# Mainland.net
KiCad netlist of a schematic drawn in EAGLE
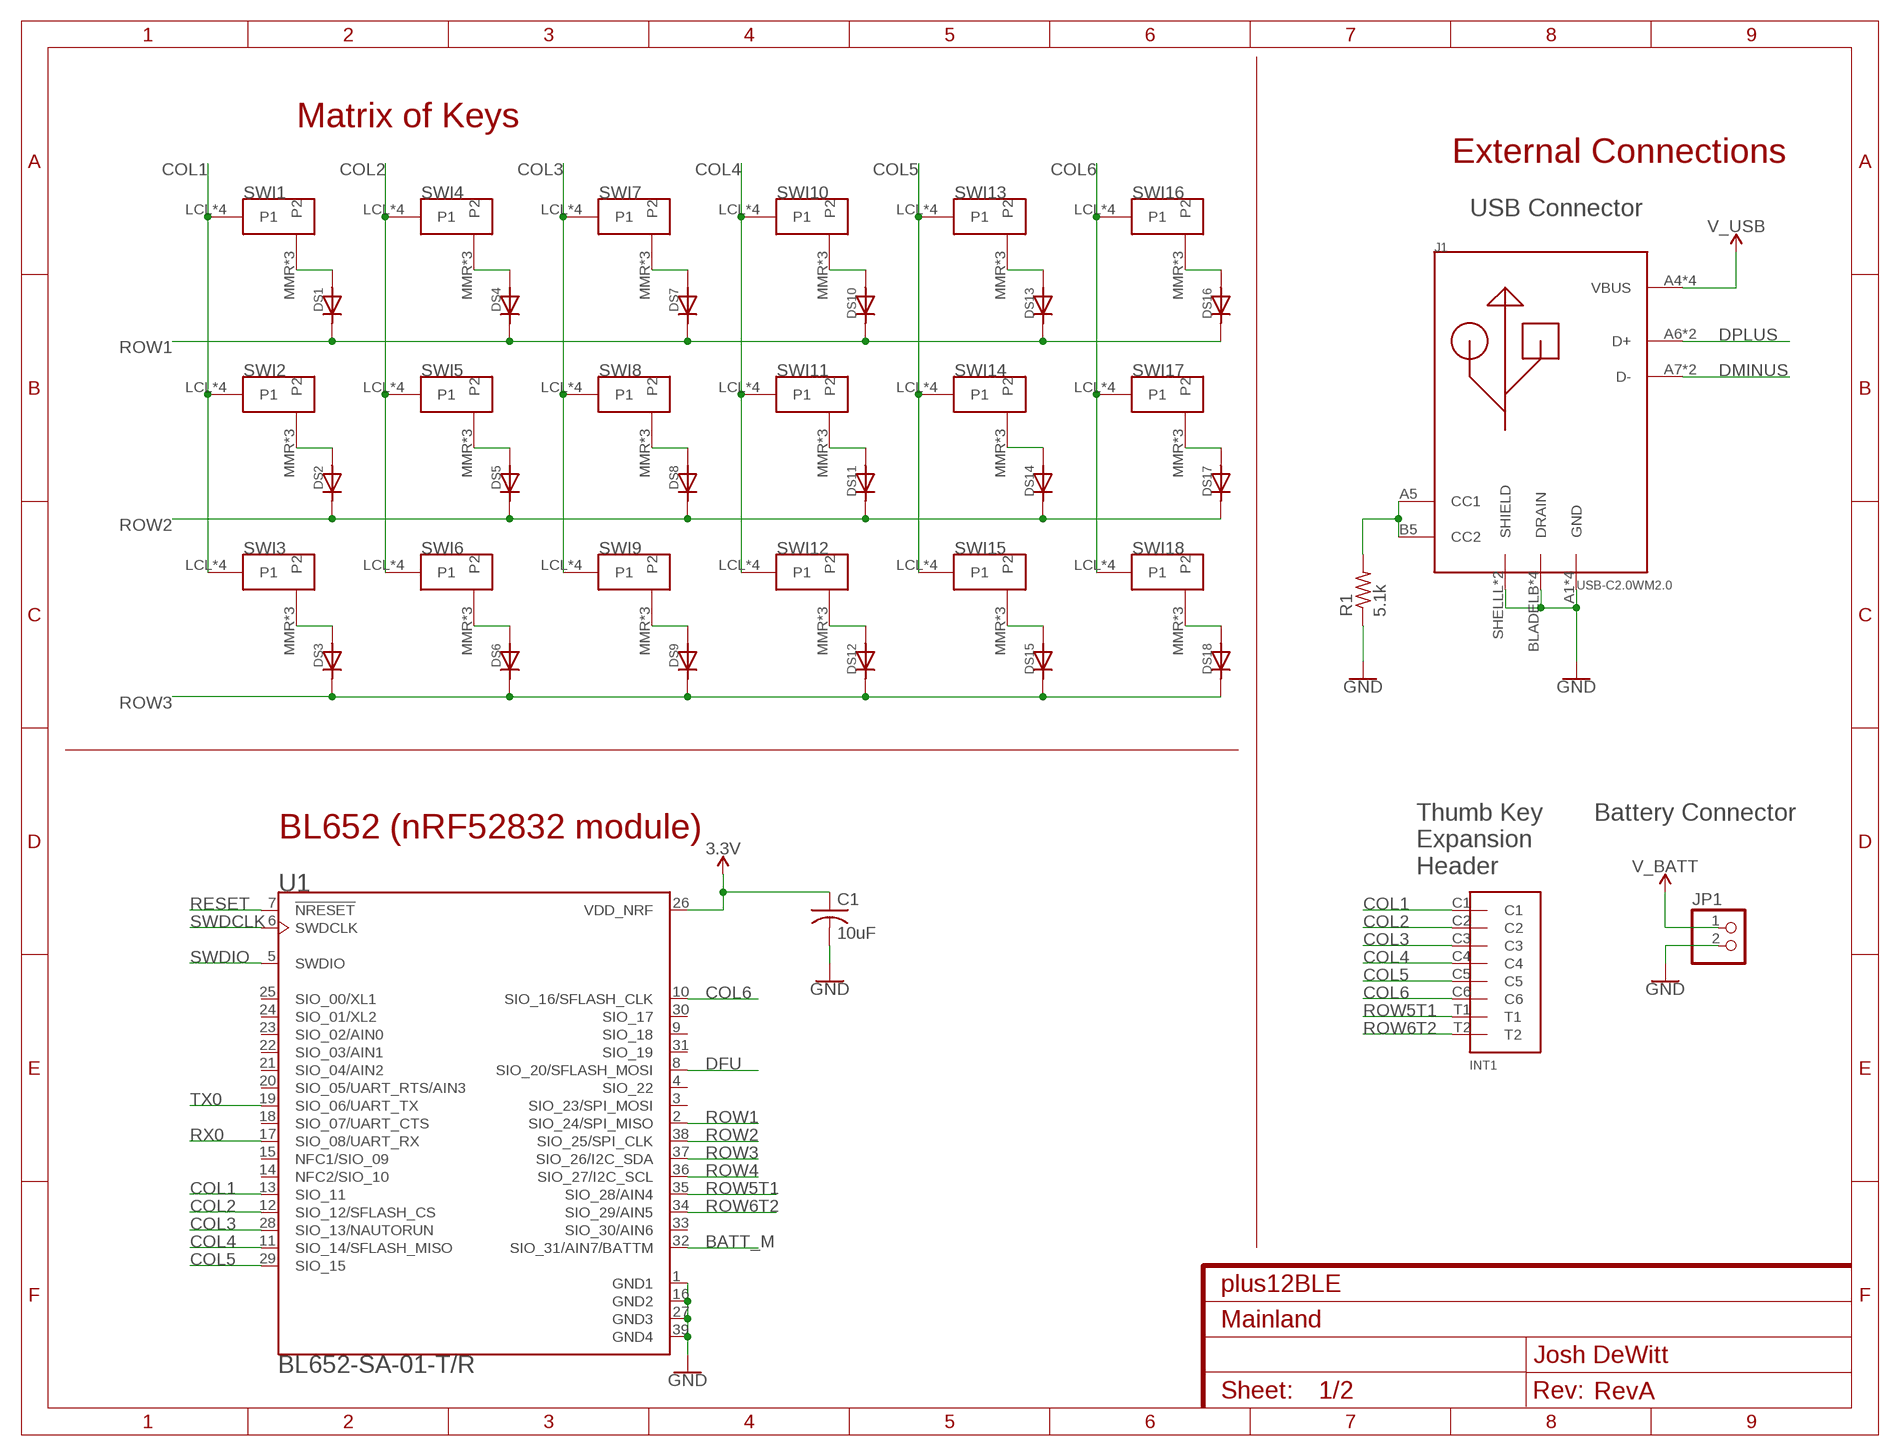
[diagram p0: schematic, sheet 1]
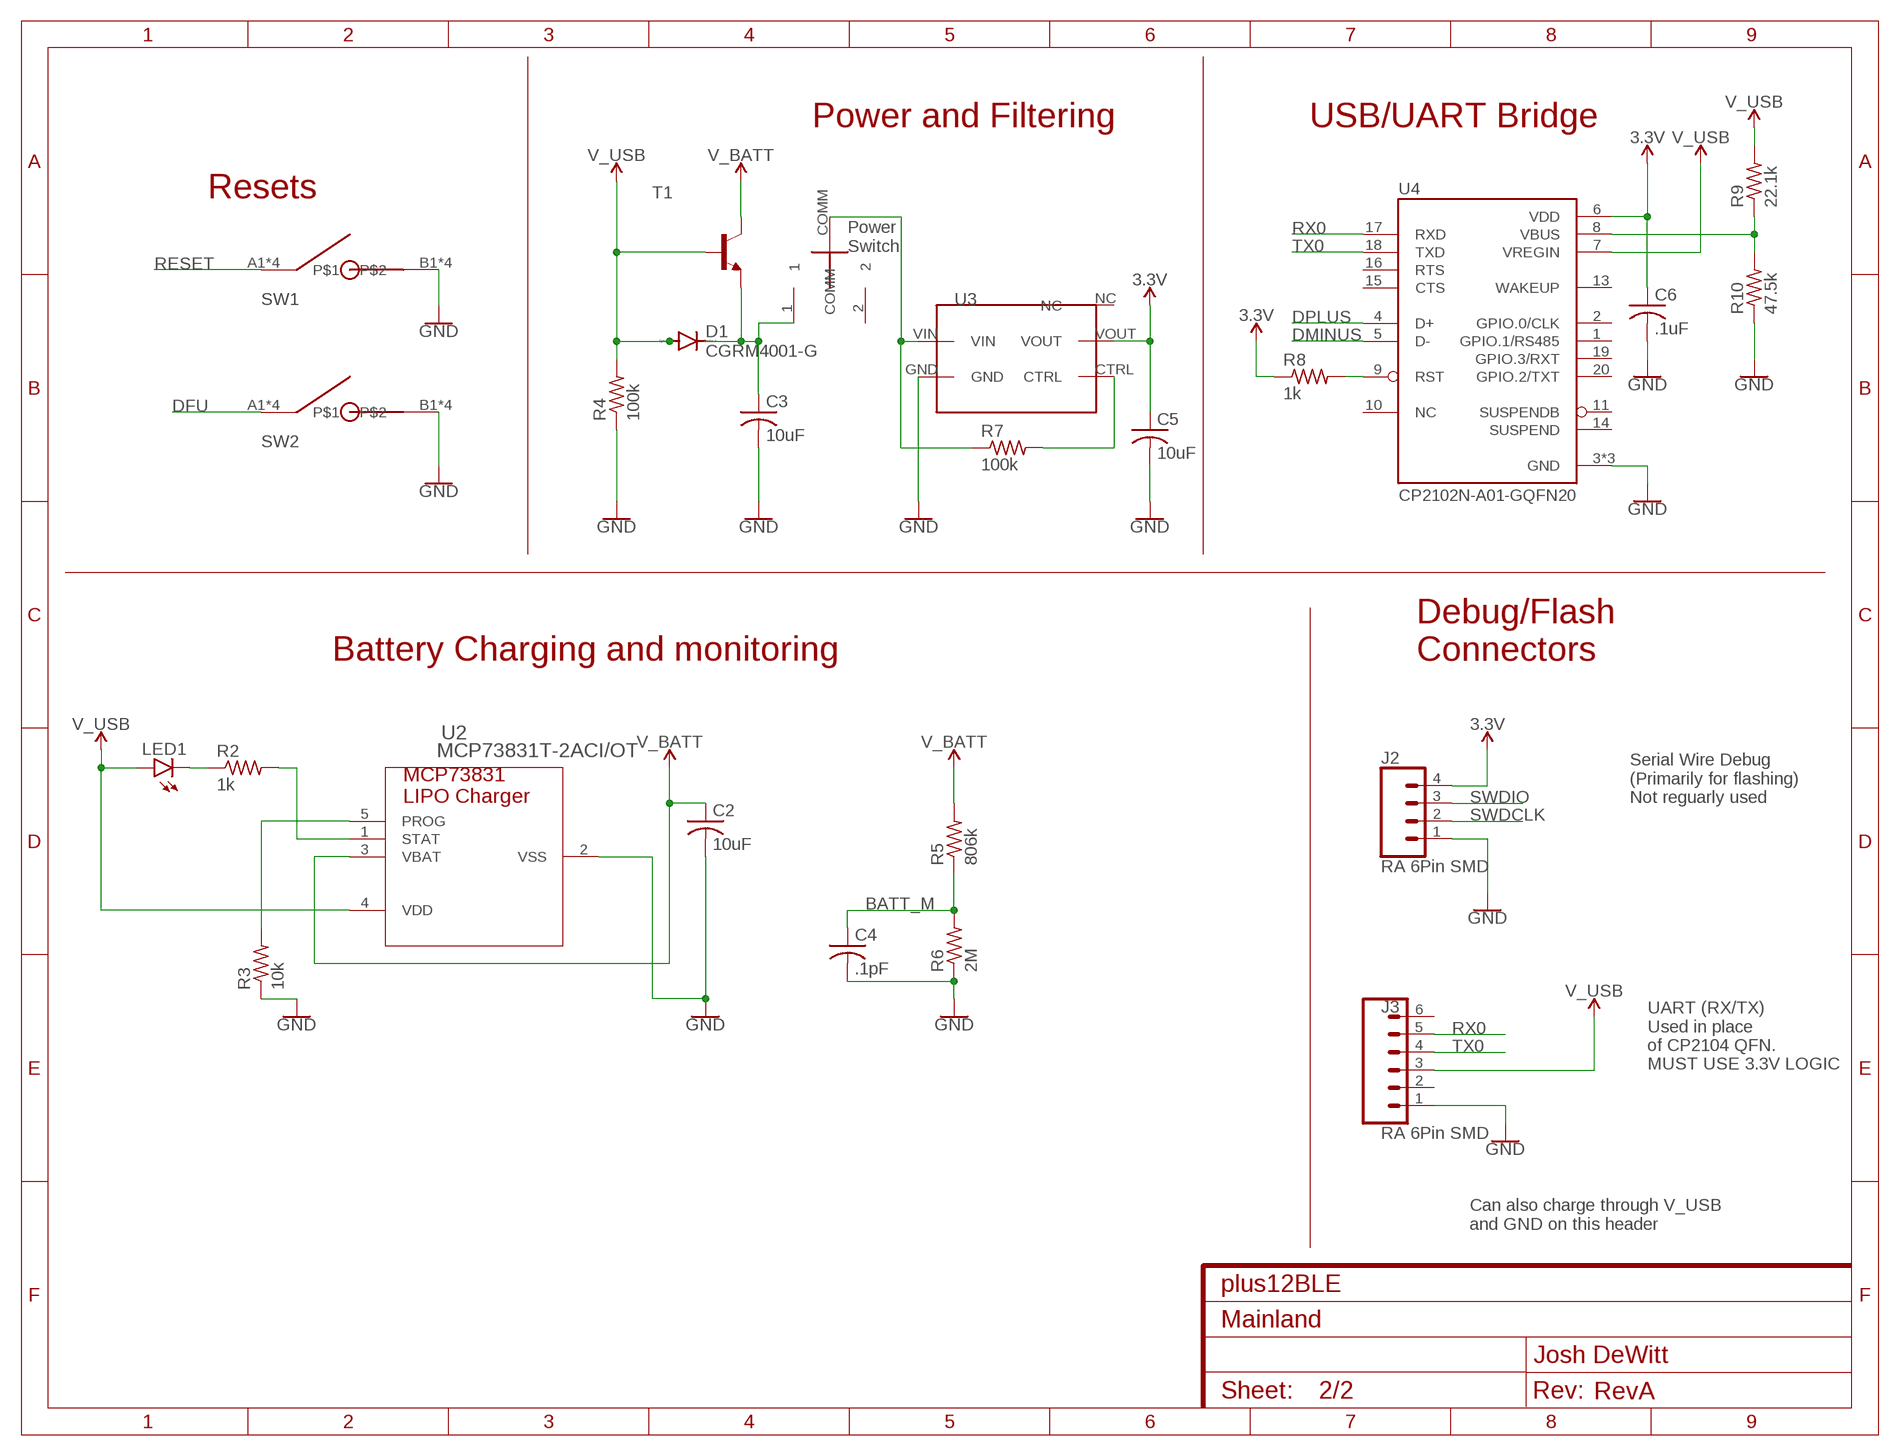
[diagram p1: schematic, sheet 2]

(export (version "E")
  (design (tool "Eeschema 10.0.6"))
  (components
    (comp (ref "C2")
      (value "10uF")
      (footprint "eagle-import:C0805K")
      (libsource (lib "eagle-import") (part "C-USC0805K"))
    )
    (comp (ref "C3")
      (value "10uF")
      (footprint "eagle-import:C0805K")
      (libsource (lib "eagle-import") (part "C-USC0805K"))
    )
    (comp (ref "C4")
      (value ".1pF")
      (footprint "eagle-import:C0603")
      (libsource (lib "eagle-import") (part "C-USC0603"))
    )
    (comp (ref "C5")
      (value "10uF")
      (footprint "eagle-import:C0805K")
      (libsource (lib "eagle-import") (part "C-USC0805K"))
    )
    (comp (ref "C6")
      (value ".1uF")
      (footprint "eagle-import:C0603")
      (libsource (lib "eagle-import") (part "C-USC0603"))
    )
    (comp (ref "D1")
      (value "CGRM4001-G")
      (footprint "eagle-import:SOD-123_MINI-SMA")
      (libsource (lib "eagle-import") (part "CGRM400-G1"))
    )
    (comp (ref "FRAME2")
      (value "FRAME_LTR_CU_MARK")
      (footprint "eagle-import:FR-LTR-ON-PCB")
      (libsource (lib "eagle-import") (part "FRAME_LTR_CU_MARK"))
    )
    (comp (ref "J2")
      (value "RA 6Pin SMD")
      (footprint "eagle-import:1X04_SMD_RA_FEMALE")
      (libsource (lib "eagle-import") (part "CONN_04SMD_RA_FEMALE"))
    )
    (comp (ref "J3")
      (value "RA 6Pin SMD")
      (footprint "eagle-import:1X06-SMD_RA_MALE")
      (libsource (lib "eagle-import") (part "CONN_06SMD"))
    )
    (comp (ref "LED1")
      (value "LEDCHIP-LED0603")
      (footprint "eagle-import:CHIP-LED0603")
      (libsource (lib "eagle-import") (part "LEDCHIP-LED0603"))
    )
    (comp (ref "R2")
      (value "1k")
      (footprint "eagle-import:R0603")
      (libsource (lib "eagle-import") (part "R-US_R0603"))
    )
    (comp (ref "R3")
      (value "10k")
      (footprint "eagle-import:R0603")
      (libsource (lib "eagle-import") (part "R-US_R0603"))
    )
    (comp (ref "R4")
      (value "100k")
      (footprint "eagle-import:R0603")
      (libsource (lib "eagle-import") (part "R-US_R0603"))
    )
    (comp (ref "R5")
      (value "806k")
      (footprint "eagle-import:R0603")
      (libsource (lib "eagle-import") (part "R-US_R0603"))
    )
    (comp (ref "R6")
      (value "2M")
      (footprint "eagle-import:R0603")
      (libsource (lib "eagle-import") (part "R-US_R0603"))
    )
    (comp (ref "R7")
      (value "100k")
      (footprint "eagle-import:R0603")
      (libsource (lib "eagle-import") (part "R-US_R0603"))
    )
    (comp (ref "R8")
      (value "1k")
      (footprint "eagle-import:R0603")
      (libsource (lib "eagle-import") (part "R-US_R0603"))
    )
    (comp (ref "R9")
      (value "22.1k")
      (footprint "eagle-import:R0603")
      (libsource (lib "eagle-import") (part "R-US_R0603"))
    )
    (comp (ref "R10")
      (value "47.5k")
      (footprint "eagle-import:R0603")
      (libsource (lib "eagle-import") (part "R-US_R0603"))
    )
    (comp (ref "SW1")
      (value "RSTSWSMALL_SMD")
      (footprint "eagle-import:EVP-BBA")
      (libsource (lib "eagle-import") (part "RSTSWSMALL_SMD"))
    )
    (comp (ref "SW2")
      (value "RSTSWSMALL_SMD")
      (footprint "eagle-import:EVP-BBA")
      (libsource (lib "eagle-import") (part "RSTSWSMALL_SMD"))
    )
    (comp (ref "SW3")
      (value "SLIDER_SWITCH")
      (footprint "eagle-import:MHSS1105")
      (libsource (lib "eagle-import") (part "SLIDER_SWITCH"))
    )
    (comp (ref "T1")
      (value "BC808-NPN-SOT23-BEC")
      (footprint "eagle-import:SOT23-BEC")
      (libsource (lib "eagle-import") (part "-NPN-SOT23-BECBC808"))
    )
    (comp (ref "U2")
      (value "MCP73831T-2ACI/OT")
      (footprint "eagle-import:SOT-23-5_MC")
      (fields (field (name "MANUFACTURER_PART_NUMBER") "MCP73831T2ACIOT"))
      (libsource (lib "eagle-import") (part "MCP73831T-2ACI/OT"))
    )
    (comp (ref "U3")
      (value "TCR2EF")
      (footprint "eagle-import:TCR2EF")
      (libsource (lib "eagle-import") (part "TCR2EF"))
    )
    (comp (ref "U4")
      (value "CP2102N-A01-GQFN20")
      (footprint "eagle-import:SILABS_QFN20")
      (fields (field (name "DIGI-KEY_PART_NUMBER") "336-3692-ND") (field (name "MF") "Silicon Labs"))
      (libsource (lib "eagle-import") (part "CP2102N-A01-GQFN20"))
    )
    (comp (ref "C1")
      (value "10uF")
      (footprint "eagle-import:C0805K")
      (libsource (lib "eagle-import") (part "C-USC0805K"))
    )
    (comp (ref "DS1")
      (value "DIODECOMBO")
      (footprint "eagle-import:DIODE_COMBO")
      (libsource (lib "eagle-import") (part "DIODECOMBO"))
    )
    (comp (ref "DS2")
      (value "DIODECOMBO")
      (footprint "eagle-import:DIODE_COMBO")
      (libsource (lib "eagle-import") (part "DIODECOMBO"))
    )
    (comp (ref "DS3")
      (value "DIODECOMBO")
      (footprint "eagle-import:DIODE_COMBO")
      (libsource (lib "eagle-import") (part "DIODECOMBO"))
    )
    (comp (ref "DS4")
      (value "DIODECOMBO")
      (footprint "eagle-import:DIODE_COMBO")
      (libsource (lib "eagle-import") (part "DIODECOMBO"))
    )
    (comp (ref "DS5")
      (value "DIODECOMBO")
      (footprint "eagle-import:DIODE_COMBO")
      (libsource (lib "eagle-import") (part "DIODECOMBO"))
    )
    (comp (ref "DS6")
      (value "DIODECOMBO")
      (footprint "eagle-import:DIODE_COMBO")
      (libsource (lib "eagle-import") (part "DIODECOMBO"))
    )
    (comp (ref "DS7")
      (value "DIODECOMBO")
      (footprint "eagle-import:DIODE_COMBO")
      (libsource (lib "eagle-import") (part "DIODECOMBO"))
    )
    (comp (ref "DS8")
      (value "DIODECOMBO")
      (footprint "eagle-import:DIODE_COMBO")
      (libsource (lib "eagle-import") (part "DIODECOMBO"))
    )
    (comp (ref "DS9")
      (value "DIODECOMBO")
      (footprint "eagle-import:DIODE_COMBO")
      (libsource (lib "eagle-import") (part "DIODECOMBO"))
    )
    (comp (ref "DS10")
      (value "DIODECOMBO")
      (footprint "eagle-import:DIODE_COMBO")
      (libsource (lib "eagle-import") (part "DIODECOMBO"))
    )
    (comp (ref "DS11")
      (value "DIODECOMBO")
      (footprint "eagle-import:DIODE_COMBO")
      (libsource (lib "eagle-import") (part "DIODECOMBO"))
    )
    (comp (ref "DS12")
      (value "DIODECOMBO")
      (footprint "eagle-import:DIODE_COMBO")
      (libsource (lib "eagle-import") (part "DIODECOMBO"))
    )
    (comp (ref "DS13")
      (value "DIODECOMBO")
      (footprint "eagle-import:DIODE_COMBO")
      (libsource (lib "eagle-import") (part "DIODECOMBO"))
    )
    (comp (ref "DS14")
      (value "DIODECOMBO")
      (footprint "eagle-import:DIODE_COMBO")
      (libsource (lib "eagle-import") (part "DIODECOMBO"))
    )
    (comp (ref "DS15")
      (value "DIODECOMBO")
      (footprint "eagle-import:DIODE_COMBO")
      (libsource (lib "eagle-import") (part "DIODECOMBO"))
    )
    (comp (ref "DS16")
      (value "DIODECOMBO")
      (footprint "eagle-import:DIODE_COMBO")
      (libsource (lib "eagle-import") (part "DIODECOMBO"))
    )
    (comp (ref "DS17")
      (value "DIODECOMBO")
      (footprint "eagle-import:DIODE_COMBO")
      (libsource (lib "eagle-import") (part "DIODECOMBO"))
    )
    (comp (ref "DS18")
      (value "DIODECOMBO")
      (footprint "eagle-import:DIODE_COMBO")
      (libsource (lib "eagle-import") (part "DIODECOMBO"))
    )
    (comp (ref "FRAME1")
      (value "FRAME_LTR_CU_MARK")
      (footprint "eagle-import:FR-LTR-ON-PCB")
      (libsource (lib "eagle-import") (part "FRAME_LTR_CU_MARK"))
    )
    (comp (ref "INT1")
      (value "INTRCNNT4X2")
      (footprint "eagle-import:INTRRIBBON")
      (libsource (lib "eagle-import") (part "INTRCNNT4X2"))
    )
    (comp (ref "J1")
      (value "USB-C2.0WM2.0")
      (footprint "eagle-import:WM17904_SIMP")
      (libsource (lib "eagle-import") (part "USB-C2.0WM2.0"))
    )
    (comp (ref "JP1")
      (value "PINHD-1X2")
      (footprint "eagle-import:1X02")
      (libsource (lib "eagle-import") (part "PINHD-1X2"))
    )
    (comp (ref "R1")
      (value "5.1k")
      (footprint "eagle-import:R0603")
      (libsource (lib "eagle-import") (part "R-US_R0603"))
    )
    (comp (ref "SWI1")
      (value "MX/ALPSDOUBLE_SLOT")
      (footprint "eagle-import:DOUBLED_SLOTS")
      (libsource (lib "eagle-import") (part "MX/ALPSDOUBLE_SLOT"))
    )
    (comp (ref "SWI2")
      (value "MX/ALPSDOUBLE_SLOT")
      (footprint "eagle-import:DOUBLED_SLOTS")
      (libsource (lib "eagle-import") (part "MX/ALPSDOUBLE_SLOT"))
    )
    (comp (ref "SWI3")
      (value "MX/ALPSDOUBLE_SLOT")
      (footprint "eagle-import:DOUBLED_SLOTS")
      (libsource (lib "eagle-import") (part "MX/ALPSDOUBLE_SLOT"))
    )
    (comp (ref "SWI4")
      (value "MX/ALPSDOUBLE_SLOT")
      (footprint "eagle-import:DOUBLED_SLOTS")
      (libsource (lib "eagle-import") (part "MX/ALPSDOUBLE_SLOT"))
    )
    (comp (ref "SWI5")
      (value "MX/ALPSDOUBLE_SLOT")
      (footprint "eagle-import:DOUBLED_SLOTS")
      (libsource (lib "eagle-import") (part "MX/ALPSDOUBLE_SLOT"))
    )
    (comp (ref "SWI6")
      (value "MX/ALPSDOUBLE_SLOT")
      (footprint "eagle-import:DOUBLED_SLOTS")
      (libsource (lib "eagle-import") (part "MX/ALPSDOUBLE_SLOT"))
    )
    (comp (ref "SWI7")
      (value "MX/ALPSDOUBLE_SLOT")
      (footprint "eagle-import:DOUBLED_SLOTS")
      (libsource (lib "eagle-import") (part "MX/ALPSDOUBLE_SLOT"))
    )
    (comp (ref "SWI8")
      (value "MX/ALPSDOUBLE_SLOT")
      (footprint "eagle-import:DOUBLED_SLOTS")
      (libsource (lib "eagle-import") (part "MX/ALPSDOUBLE_SLOT"))
    )
    (comp (ref "SWI9")
      (value "MX/ALPSDOUBLE_SLOT")
      (footprint "eagle-import:DOUBLED_SLOTS")
      (libsource (lib "eagle-import") (part "MX/ALPSDOUBLE_SLOT"))
    )
    (comp (ref "SWI10")
      (value "MX/ALPSDOUBLE_SLOT")
      (footprint "eagle-import:DOUBLED_SLOTS")
      (libsource (lib "eagle-import") (part "MX/ALPSDOUBLE_SLOT"))
    )
    (comp (ref "SWI11")
      (value "MX/ALPSDOUBLE_SLOT")
      (footprint "eagle-import:DOUBLED_SLOTS")
      (libsource (lib "eagle-import") (part "MX/ALPSDOUBLE_SLOT"))
    )
    (comp (ref "SWI12")
      (value "MX/ALPSDOUBLE_SLOT")
      (footprint "eagle-import:DOUBLED_SLOTS")
      (libsource (lib "eagle-import") (part "MX/ALPSDOUBLE_SLOT"))
    )
    (comp (ref "SWI13")
      (value "MX/ALPSDOUBLE_SLOT")
      (footprint "eagle-import:DOUBLED_SLOTS")
      (libsource (lib "eagle-import") (part "MX/ALPSDOUBLE_SLOT"))
    )
    (comp (ref "SWI14")
      (value "MX/ALPSDOUBLE_SLOT")
      (footprint "eagle-import:DOUBLED_SLOTS")
      (libsource (lib "eagle-import") (part "MX/ALPSDOUBLE_SLOT"))
    )
    (comp (ref "SWI15")
      (value "MX/ALPSDOUBLE_SLOT")
      (footprint "eagle-import:DOUBLED_SLOTS")
      (libsource (lib "eagle-import") (part "MX/ALPSDOUBLE_SLOT"))
    )
    (comp (ref "SWI16")
      (value "MX/ALPSDOUBLE_SLOT")
      (footprint "eagle-import:DOUBLED_SLOTS")
      (libsource (lib "eagle-import") (part "MX/ALPSDOUBLE_SLOT"))
    )
    (comp (ref "SWI17")
      (value "MX/ALPSDOUBLE_SLOT")
      (footprint "eagle-import:DOUBLED_SLOTS")
      (libsource (lib "eagle-import") (part "MX/ALPSDOUBLE_SLOT"))
    )
    (comp (ref "SWI18")
      (value "MX/ALPSDOUBLE_SLOT")
      (footprint "eagle-import:DOUBLED_SLOTS")
      (libsource (lib "eagle-import") (part "MX/ALPSDOUBLE_SLOT"))
    )
    (comp (ref "U1")
      (value "BL652-SA-01-T/R")
      (footprint "eagle-import:XCVR_BL652-SA-01-T_R")
      (fields (field (name "DIGI-KEY_PART_NUMBER") "BL652-SA-01-CT-ND") (field (name "MF") "Laird -"))
      (libsource (lib "eagle-import") (part "BL652-SA-01-T/R"))
    )
  )
  (nets
    (net (code "1") (name "3.3V") (class "Default")
      (node (ref "C1") (pin "1") (pinfunction "1_1") (pintype "passive"))
      (node (ref "C5") (pin "1") (pinfunction "1_1") (pintype "passive"))
      (node (ref "C6") (pin "1") (pinfunction "1_1") (pintype "passive"))
      (node (ref "J2") (pin "4") (pinfunction "4_4") (pintype "passive"))
      (node (ref "R8") (pin "1") (pinfunction "1_1") (pintype "passive"))
      (node (ref "U1") (pin "26") (pinfunction "VDD_NRF_26") (pintype "power_in"))
      (node (ref "U3") (pin "VOUT") (pinfunction "VOUT_VOUT") (pintype "power_in"))
      (node (ref "U4") (pin "6") (pinfunction "VDD_6") (pintype "power_in"))
    )
    (net (code "2") (name "BATT_M") (class "Default")
      (node (ref "C4") (pin "1") (pinfunction "1_1") (pintype "passive"))
      (node (ref "R5") (pin "1") (pinfunction "1_1") (pintype "passive"))
      (node (ref "R6") (pin "2") (pinfunction "2_2") (pintype "passive"))
      (node (ref "U1") (pin "32") (pinfunction "SIO_31/AIN7/BATTM_32") (pintype "bidirectional"))
    )
    (net (code "3") (name "COL1") (class "Default")
      (node (ref "INT1") (pin "C1") (pinfunction "C1_C1") (pintype "bidirectional"))
      (node (ref "SWI1") (pin "LCL") (pinfunction "P1_LCL") (pintype "bidirectional"))
      (node (ref "SWI1") (pin "LLP") (pinfunction "P1_LLP") (pintype "bidirectional"))
      (node (ref "SWI1") (pin "LRLP") (pinfunction "P1_LRLP") (pintype "bidirectional"))
      (node (ref "SWI1") (pin "MML") (pinfunction "P1_MML") (pintype "bidirectional"))
      (node (ref "SWI2") (pin "LCL") (pinfunction "P1_LCL") (pintype "bidirectional"))
      (node (ref "SWI2") (pin "LLP") (pinfunction "P1_LLP") (pintype "bidirectional"))
      (node (ref "SWI2") (pin "LRLP") (pinfunction "P1_LRLP") (pintype "bidirectional"))
      (node (ref "SWI2") (pin "MML") (pinfunction "P1_MML") (pintype "bidirectional"))
      (node (ref "SWI3") (pin "LCL") (pinfunction "P1_LCL") (pintype "bidirectional"))
      (node (ref "SWI3") (pin "LLP") (pinfunction "P1_LLP") (pintype "bidirectional"))
      (node (ref "SWI3") (pin "LRLP") (pinfunction "P1_LRLP") (pintype "bidirectional"))
      (node (ref "SWI3") (pin "MML") (pinfunction "P1_MML") (pintype "bidirectional"))
      (node (ref "U1") (pin "13") (pinfunction "SIO_11_13") (pintype "bidirectional"))
    )
    (net (code "4") (name "COL2") (class "Default")
      (node (ref "INT1") (pin "C2") (pinfunction "C2_C2") (pintype "bidirectional"))
      (node (ref "SWI4") (pin "LCL") (pinfunction "P1_LCL") (pintype "bidirectional"))
      (node (ref "SWI4") (pin "LLP") (pinfunction "P1_LLP") (pintype "bidirectional"))
      (node (ref "SWI4") (pin "LRLP") (pinfunction "P1_LRLP") (pintype "bidirectional"))
      (node (ref "SWI4") (pin "MML") (pinfunction "P1_MML") (pintype "bidirectional"))
      (node (ref "SWI5") (pin "LCL") (pinfunction "P1_LCL") (pintype "bidirectional"))
      (node (ref "SWI5") (pin "LLP") (pinfunction "P1_LLP") (pintype "bidirectional"))
      (node (ref "SWI5") (pin "LRLP") (pinfunction "P1_LRLP") (pintype "bidirectional"))
      (node (ref "SWI5") (pin "MML") (pinfunction "P1_MML") (pintype "bidirectional"))
      (node (ref "SWI6") (pin "LCL") (pinfunction "P1_LCL") (pintype "bidirectional"))
      (node (ref "SWI6") (pin "LLP") (pinfunction "P1_LLP") (pintype "bidirectional"))
      (node (ref "SWI6") (pin "LRLP") (pinfunction "P1_LRLP") (pintype "bidirectional"))
      (node (ref "SWI6") (pin "MML") (pinfunction "P1_MML") (pintype "bidirectional"))
      (node (ref "U1") (pin "12") (pinfunction "SIO_12/SFLASH_CS_12") (pintype "bidirectional"))
    )
    (net (code "5") (name "COL3") (class "Default")
      (node (ref "INT1") (pin "C3") (pinfunction "C3_C3") (pintype "bidirectional"))
      (node (ref "SWI7") (pin "LCL") (pinfunction "P1_LCL") (pintype "bidirectional"))
      (node (ref "SWI7") (pin "LLP") (pinfunction "P1_LLP") (pintype "bidirectional"))
      (node (ref "SWI7") (pin "LRLP") (pinfunction "P1_LRLP") (pintype "bidirectional"))
      (node (ref "SWI7") (pin "MML") (pinfunction "P1_MML") (pintype "bidirectional"))
      (node (ref "SWI8") (pin "LCL") (pinfunction "P1_LCL") (pintype "bidirectional"))
      (node (ref "SWI8") (pin "LLP") (pinfunction "P1_LLP") (pintype "bidirectional"))
      (node (ref "SWI8") (pin "LRLP") (pinfunction "P1_LRLP") (pintype "bidirectional"))
      (node (ref "SWI8") (pin "MML") (pinfunction "P1_MML") (pintype "bidirectional"))
      (node (ref "SWI9") (pin "LCL") (pinfunction "P1_LCL") (pintype "bidirectional"))
      (node (ref "SWI9") (pin "LLP") (pinfunction "P1_LLP") (pintype "bidirectional"))
      (node (ref "SWI9") (pin "LRLP") (pinfunction "P1_LRLP") (pintype "bidirectional"))
      (node (ref "SWI9") (pin "MML") (pinfunction "P1_MML") (pintype "bidirectional"))
      (node (ref "U1") (pin "28") (pinfunction "SIO_13/NAUTORUN_28") (pintype "bidirectional"))
    )
    (net (code "6") (name "COL4") (class "Default")
      (node (ref "INT1") (pin "C4") (pinfunction "C4_C4") (pintype "bidirectional"))
      (node (ref "SWI10") (pin "LCL") (pinfunction "P1_LCL") (pintype "bidirectional"))
      (node (ref "SWI10") (pin "LLP") (pinfunction "P1_LLP") (pintype "bidirectional"))
      (node (ref "SWI10") (pin "LRLP") (pinfunction "P1_LRLP") (pintype "bidirectional"))
      (node (ref "SWI10") (pin "MML") (pinfunction "P1_MML") (pintype "bidirectional"))
      (node (ref "SWI11") (pin "LCL") (pinfunction "P1_LCL") (pintype "bidirectional"))
      (node (ref "SWI11") (pin "LLP") (pinfunction "P1_LLP") (pintype "bidirectional"))
      (node (ref "SWI11") (pin "LRLP") (pinfunction "P1_LRLP") (pintype "bidirectional"))
      (node (ref "SWI11") (pin "MML") (pinfunction "P1_MML") (pintype "bidirectional"))
      (node (ref "SWI12") (pin "LCL") (pinfunction "P1_LCL") (pintype "bidirectional"))
      (node (ref "SWI12") (pin "LLP") (pinfunction "P1_LLP") (pintype "bidirectional"))
      (node (ref "SWI12") (pin "LRLP") (pinfunction "P1_LRLP") (pintype "bidirectional"))
      (node (ref "SWI12") (pin "MML") (pinfunction "P1_MML") (pintype "bidirectional"))
      (node (ref "U1") (pin "11") (pinfunction "SIO_14/SFLASH_MISO_11") (pintype "bidirectional"))
    )
    (net (code "7") (name "COL5") (class "Default")
      (node (ref "INT1") (pin "C5") (pinfunction "C5_C5") (pintype "bidirectional"))
      (node (ref "SWI13") (pin "LCL") (pinfunction "P1_LCL") (pintype "bidirectional"))
      (node (ref "SWI13") (pin "LLP") (pinfunction "P1_LLP") (pintype "bidirectional"))
      (node (ref "SWI13") (pin "LRLP") (pinfunction "P1_LRLP") (pintype "bidirectional"))
      (node (ref "SWI13") (pin "MML") (pinfunction "P1_MML") (pintype "bidirectional"))
      (node (ref "SWI14") (pin "LCL") (pinfunction "P1_LCL") (pintype "bidirectional"))
      (node (ref "SWI14") (pin "LLP") (pinfunction "P1_LLP") (pintype "bidirectional"))
      (node (ref "SWI14") (pin "LRLP") (pinfunction "P1_LRLP") (pintype "bidirectional"))
      (node (ref "SWI14") (pin "MML") (pinfunction "P1_MML") (pintype "bidirectional"))
      (node (ref "SWI15") (pin "LCL") (pinfunction "P1_LCL") (pintype "bidirectional"))
      (node (ref "SWI15") (pin "LLP") (pinfunction "P1_LLP") (pintype "bidirectional"))
      (node (ref "SWI15") (pin "LRLP") (pinfunction "P1_LRLP") (pintype "bidirectional"))
      (node (ref "SWI15") (pin "MML") (pinfunction "P1_MML") (pintype "bidirectional"))
      (node (ref "U1") (pin "29") (pinfunction "SIO_15_29") (pintype "bidirectional"))
    )
    (net (code "8") (name "COL6") (class "Default")
      (node (ref "INT1") (pin "C6") (pinfunction "C6_C6") (pintype "bidirectional"))
      (node (ref "SWI16") (pin "LCL") (pinfunction "P1_LCL") (pintype "bidirectional"))
      (node (ref "SWI16") (pin "LLP") (pinfunction "P1_LLP") (pintype "bidirectional"))
      (node (ref "SWI16") (pin "LRLP") (pinfunction "P1_LRLP") (pintype "bidirectional"))
      (node (ref "SWI16") (pin "MML") (pinfunction "P1_MML") (pintype "bidirectional"))
      (node (ref "SWI17") (pin "LCL") (pinfunction "P1_LCL") (pintype "bidirectional"))
      (node (ref "SWI17") (pin "LLP") (pinfunction "P1_LLP") (pintype "bidirectional"))
      (node (ref "SWI17") (pin "LRLP") (pinfunction "P1_LRLP") (pintype "bidirectional"))
      (node (ref "SWI17") (pin "MML") (pinfunction "P1_MML") (pintype "bidirectional"))
      (node (ref "SWI18") (pin "LCL") (pinfunction "P1_LCL") (pintype "bidirectional"))
      (node (ref "SWI18") (pin "LLP") (pinfunction "P1_LLP") (pintype "bidirectional"))
      (node (ref "SWI18") (pin "LRLP") (pinfunction "P1_LRLP") (pintype "bidirectional"))
      (node (ref "SWI18") (pin "MML") (pinfunction "P1_MML") (pintype "bidirectional"))
      (node (ref "U1") (pin "10") (pinfunction "SIO_16/SFLASH_CLK_10") (pintype "bidirectional"))
    )
    (net (code "9") (name "DFU") (class "Default")
      (node (ref "SW2") (pin "A1") (pinfunction "P$1_A1") (pintype "bidirectional"))
      (node (ref "SW2") (pin "A2") (pinfunction "P$1_A2") (pintype "bidirectional"))
      (node (ref "SW2") (pin "A3") (pinfunction "P$1_A3") (pintype "bidirectional"))
      (node (ref "SW2") (pin "A4") (pinfunction "P$1_A4") (pintype "bidirectional"))
      (node (ref "U1") (pin "8") (pinfunction "SIO_20/SFLASH_MOSI_8") (pintype "bidirectional"))
    )
    (net (code "10") (name "DMINUS") (class "Default")
      (node (ref "J1") (pin "A7") (pinfunction "D-_A7") (pintype "bidirectional"))
      (node (ref "J1") (pin "B7") (pinfunction "D-_B7") (pintype "bidirectional"))
      (node (ref "U4") (pin "5") (pinfunction "D-_5") (pintype "bidirectional"))
    )
    (net (code "11") (name "DPLUS") (class "Default")
      (node (ref "J1") (pin "A6") (pinfunction "D+_A6") (pintype "bidirectional"))
      (node (ref "J1") (pin "B6") (pinfunction "D+_B6") (pintype "bidirectional"))
      (node (ref "U4") (pin "4") (pinfunction "D+_4") (pintype "bidirectional"))
    )
    (net (code "12") (name "GND") (class "Default")
      (node (ref "C1") (pin "2") (pinfunction "2_2") (pintype "passive"))
      (node (ref "C2") (pin "2") (pinfunction "2_2") (pintype "passive"))
      (node (ref "C3") (pin "2") (pinfunction "2_2") (pintype "passive"))
      (node (ref "C4") (pin "2") (pinfunction "2_2") (pintype "passive"))
      (node (ref "C5") (pin "2") (pinfunction "2_2") (pintype "passive"))
      (node (ref "C6") (pin "2") (pinfunction "2_2") (pintype "passive"))
      (node (ref "J1") (pin "A1") (pinfunction "GND_A1") (pintype "bidirectional"))
      (node (ref "J1") (pin "A12") (pinfunction "GND_A12") (pintype "bidirectional"))
      (node (ref "J1") (pin "B1") (pinfunction "GND_B1") (pintype "bidirectional"))
      (node (ref "J1") (pin "B12") (pinfunction "GND_B12") (pintype "bidirectional"))
      (node (ref "J1") (pin "BLADELB") (pinfunction "DRAIN_BLADELB") (pintype "bidirectional"))
      (node (ref "J1") (pin "BLADELF") (pinfunction "DRAIN_BLADELF") (pintype "bidirectional"))
      (node (ref "J1") (pin "BLADERB") (pinfunction "DRAIN_BLADERB") (pintype "bidirectional"))
      (node (ref "J1") (pin "BLADERF") (pinfunction "DRAIN_BLADERF") (pintype "bidirectional"))
      (node (ref "J1") (pin "SHELLL") (pinfunction "SHIELD_SHELLL") (pintype "bidirectional"))
      (node (ref "J1") (pin "SHELLR") (pinfunction "SHIELD_SHELLR") (pintype "bidirectional"))
      (node (ref "J2") (pin "1") (pinfunction "1_1") (pintype "passive"))
      (node (ref "J3") (pin "1") (pinfunction "1_1") (pintype "passive"))
      (node (ref "JP1") (pin "2") (pinfunction "2_2") (pintype "passive"))
      (node (ref "R1") (pin "1") (pinfunction "1_1") (pintype "passive"))
      (node (ref "R10") (pin "1") (pinfunction "1_1") (pintype "passive"))
      (node (ref "R3") (pin "1") (pinfunction "1_1") (pintype "passive"))
      (node (ref "R4") (pin "1") (pinfunction "1_1") (pintype "passive"))
      (node (ref "R6") (pin "1") (pinfunction "1_1") (pintype "passive"))
      (node (ref "SW1") (pin "B1") (pinfunction "P$2_B1") (pintype "bidirectional"))
      (node (ref "SW1") (pin "B2") (pinfunction "P$2_B2") (pintype "bidirectional"))
      (node (ref "SW1") (pin "B3") (pinfunction "P$2_B3") (pintype "bidirectional"))
      (node (ref "SW1") (pin "B4") (pinfunction "P$2_B4") (pintype "bidirectional"))
      (node (ref "SW2") (pin "B1") (pinfunction "P$2_B1") (pintype "bidirectional"))
      (node (ref "SW2") (pin "B2") (pinfunction "P$2_B2") (pintype "bidirectional"))
      (node (ref "SW2") (pin "B3") (pinfunction "P$2_B3") (pintype "bidirectional"))
      (node (ref "SW2") (pin "B4") (pinfunction "P$2_B4") (pintype "bidirectional"))
      (node (ref "U1") (pin "1") (pinfunction "GND1_1") (pintype "power_in"))
      (node (ref "U1") (pin "16") (pinfunction "GND2_16") (pintype "power_in"))
      (node (ref "U1") (pin "27") (pinfunction "GND3_27") (pintype "power_in"))
      (node (ref "U1") (pin "39") (pinfunction "GND4_39") (pintype "power_in"))
      (node (ref "U2") (pin "2") (pinfunction "VSS_2") (pintype "passive"))
      (node (ref "U3") (pin "GND") (pinfunction "GND_GND") (pintype "power_in"))
      (node (ref "U4") (pin "12") (pinfunction "GND_12") (pintype "power_in"))
      (node (ref "U4") (pin "21") (pinfunction "GND_21") (pintype "power_in"))
      (node (ref "U4") (pin "3") (pinfunction "GND_3") (pintype "power_in"))
    )
    (net (code "13") (name "Net-(C3-Pad1)") (class "Default")
      (node (ref "C3") (pin "1") (pinfunction "1_1") (pintype "passive"))
      (node (ref "D1") (pin "C") (pinfunction "C_C") (pintype "passive"))
      (node (ref "SW3") (pin "1") (pinfunction "1_1") (pintype "passive"))
      (node (ref "T1") (pin "E") (pinfunction "E_E") (pintype "passive"))
    )
    (net (code "14") (name "Net-(DS1-AN-PadANOST)") (class "Default")
      (node (ref "DS1") (pin "ANOST") (pinfunction "AN_ANOST") (pintype "bidirectional"))
      (node (ref "DS1") (pin "ANOT") (pinfunction "AN_ANOT") (pintype "bidirectional"))
      (node (ref "SWI1") (pin "MMR") (pinfunction "P2_MMR") (pintype "bidirectional"))
      (node (ref "SWI1") (pin "RCL") (pinfunction "P2_RCL") (pintype "bidirectional"))
      (node (ref "SWI1") (pin "RLMID") (pinfunction "P2_RLMID") (pintype "bidirectional"))
    )
    (net (code "15") (name "Net-(DS2-AN-PadANOST)") (class "Default")
      (node (ref "DS2") (pin "ANOST") (pinfunction "AN_ANOST") (pintype "bidirectional"))
      (node (ref "DS2") (pin "ANOT") (pinfunction "AN_ANOT") (pintype "bidirectional"))
      (node (ref "SWI2") (pin "MMR") (pinfunction "P2_MMR") (pintype "bidirectional"))
      (node (ref "SWI2") (pin "RCL") (pinfunction "P2_RCL") (pintype "bidirectional"))
      (node (ref "SWI2") (pin "RLMID") (pinfunction "P2_RLMID") (pintype "bidirectional"))
    )
    (net (code "16") (name "Net-(DS3-AN-PadANOST)") (class "Default")
      (node (ref "DS3") (pin "ANOST") (pinfunction "AN_ANOST") (pintype "bidirectional"))
      (node (ref "DS3") (pin "ANOT") (pinfunction "AN_ANOT") (pintype "bidirectional"))
      (node (ref "SWI3") (pin "MMR") (pinfunction "P2_MMR") (pintype "bidirectional"))
      (node (ref "SWI3") (pin "RCL") (pinfunction "P2_RCL") (pintype "bidirectional"))
      (node (ref "SWI3") (pin "RLMID") (pinfunction "P2_RLMID") (pintype "bidirectional"))
    )
    (net (code "17") (name "Net-(DS4-AN-PadANOST)") (class "Default")
      (node (ref "DS4") (pin "ANOST") (pinfunction "AN_ANOST") (pintype "bidirectional"))
      (node (ref "DS4") (pin "ANOT") (pinfunction "AN_ANOT") (pintype "bidirectional"))
      (node (ref "SWI4") (pin "MMR") (pinfunction "P2_MMR") (pintype "bidirectional"))
      (node (ref "SWI4") (pin "RCL") (pinfunction "P2_RCL") (pintype "bidirectional"))
      (node (ref "SWI4") (pin "RLMID") (pinfunction "P2_RLMID") (pintype "bidirectional"))
    )
    (net (code "18") (name "Net-(DS5-AN-PadANOST)") (class "Default")
      (node (ref "DS5") (pin "ANOST") (pinfunction "AN_ANOST") (pintype "bidirectional"))
      (node (ref "DS5") (pin "ANOT") (pinfunction "AN_ANOT") (pintype "bidirectional"))
      (node (ref "SWI5") (pin "MMR") (pinfunction "P2_MMR") (pintype "bidirectional"))
      (node (ref "SWI5") (pin "RCL") (pinfunction "P2_RCL") (pintype "bidirectional"))
      (node (ref "SWI5") (pin "RLMID") (pinfunction "P2_RLMID") (pintype "bidirectional"))
    )
    (net (code "19") (name "Net-(DS6-AN-PadANOST)") (class "Default")
      (node (ref "DS6") (pin "ANOST") (pinfunction "AN_ANOST") (pintype "bidirectional"))
      (node (ref "DS6") (pin "ANOT") (pinfunction "AN_ANOT") (pintype "bidirectional"))
      (node (ref "SWI6") (pin "MMR") (pinfunction "P2_MMR") (pintype "bidirectional"))
      (node (ref "SWI6") (pin "RCL") (pinfunction "P2_RCL") (pintype "bidirectional"))
      (node (ref "SWI6") (pin "RLMID") (pinfunction "P2_RLMID") (pintype "bidirectional"))
    )
    (net (code "20") (name "Net-(DS7-AN-PadANOST)") (class "Default")
      (node (ref "DS7") (pin "ANOST") (pinfunction "AN_ANOST") (pintype "bidirectional"))
      (node (ref "DS7") (pin "ANOT") (pinfunction "AN_ANOT") (pintype "bidirectional"))
      (node (ref "SWI7") (pin "MMR") (pinfunction "P2_MMR") (pintype "bidirectional"))
      (node (ref "SWI7") (pin "RCL") (pinfunction "P2_RCL") (pintype "bidirectional"))
      (node (ref "SWI7") (pin "RLMID") (pinfunction "P2_RLMID") (pintype "bidirectional"))
    )
    (net (code "21") (name "Net-(DS8-AN-PadANOST)") (class "Default")
      (node (ref "DS8") (pin "ANOST") (pinfunction "AN_ANOST") (pintype "bidirectional"))
      (node (ref "DS8") (pin "ANOT") (pinfunction "AN_ANOT") (pintype "bidirectional"))
      (node (ref "SWI8") (pin "MMR") (pinfunction "P2_MMR") (pintype "bidirectional"))
      (node (ref "SWI8") (pin "RCL") (pinfunction "P2_RCL") (pintype "bidirectional"))
      (node (ref "SWI8") (pin "RLMID") (pinfunction "P2_RLMID") (pintype "bidirectional"))
    )
    (net (code "22") (name "Net-(DS9-AN-PadANOST)") (class "Default")
      (node (ref "DS9") (pin "ANOST") (pinfunction "AN_ANOST") (pintype "bidirectional"))
      (node (ref "DS9") (pin "ANOT") (pinfunction "AN_ANOT") (pintype "bidirectional"))
      (node (ref "SWI9") (pin "MMR") (pinfunction "P2_MMR") (pintype "bidirectional"))
      (node (ref "SWI9") (pin "RCL") (pinfunction "P2_RCL") (pintype "bidirectional"))
      (node (ref "SWI9") (pin "RLMID") (pinfunction "P2_RLMID") (pintype "bidirectional"))
    )
    (net (code "23") (name "Net-(DS10-AN-PadANOST)") (class "Default")
      (node (ref "DS10") (pin "ANOST") (pinfunction "AN_ANOST") (pintype "bidirectional"))
      (node (ref "DS10") (pin "ANOT") (pinfunction "AN_ANOT") (pintype "bidirectional"))
      (node (ref "SWI10") (pin "MMR") (pinfunction "P2_MMR") (pintype "bidirectional"))
      (node (ref "SWI10") (pin "RCL") (pinfunction "P2_RCL") (pintype "bidirectional"))
      (node (ref "SWI10") (pin "RLMID") (pinfunction "P2_RLMID") (pintype "bidirectional"))
    )
    (net (code "24") (name "Net-(DS11-AN-PadANOST)") (class "Default")
      (node (ref "DS11") (pin "ANOST") (pinfunction "AN_ANOST") (pintype "bidirectional"))
      (node (ref "DS11") (pin "ANOT") (pinfunction "AN_ANOT") (pintype "bidirectional"))
      (node (ref "SWI11") (pin "MMR") (pinfunction "P2_MMR") (pintype "bidirectional"))
      (node (ref "SWI11") (pin "RCL") (pinfunction "P2_RCL") (pintype "bidirectional"))
      (node (ref "SWI11") (pin "RLMID") (pinfunction "P2_RLMID") (pintype "bidirectional"))
    )
    (net (code "25") (name "Net-(DS12-AN-PadANOST)") (class "Default")
      (node (ref "DS12") (pin "ANOST") (pinfunction "AN_ANOST") (pintype "bidirectional"))
      (node (ref "DS12") (pin "ANOT") (pinfunction "AN_ANOT") (pintype "bidirectional"))
      (node (ref "SWI12") (pin "MMR") (pinfunction "P2_MMR") (pintype "bidirectional"))
      (node (ref "SWI12") (pin "RCL") (pinfunction "P2_RCL") (pintype "bidirectional"))
      (node (ref "SWI12") (pin "RLMID") (pinfunction "P2_RLMID") (pintype "bidirectional"))
    )
    (net (code "26") (name "Net-(DS13-AN-PadANOST)") (class "Default")
      (node (ref "DS13") (pin "ANOST") (pinfunction "AN_ANOST") (pintype "bidirectional"))
      (node (ref "DS13") (pin "ANOT") (pinfunction "AN_ANOT") (pintype "bidirectional"))
      (node (ref "SWI13") (pin "MMR") (pinfunction "P2_MMR") (pintype "bidirectional"))
      (node (ref "SWI13") (pin "RCL") (pinfunction "P2_RCL") (pintype "bidirectional"))
      (node (ref "SWI13") (pin "RLMID") (pinfunction "P2_RLMID") (pintype "bidirectional"))
    )
    (net (code "27") (name "Net-(DS14-AN-PadANOST)") (class "Default")
      (node (ref "DS14") (pin "ANOST") (pinfunction "AN_ANOST") (pintype "bidirectional"))
      (node (ref "DS14") (pin "ANOT") (pinfunction "AN_ANOT") (pintype "bidirectional"))
      (node (ref "SWI14") (pin "MMR") (pinfunction "P2_MMR") (pintype "bidirectional"))
      (node (ref "SWI14") (pin "RCL") (pinfunction "P2_RCL") (pintype "bidirectional"))
      (node (ref "SWI14") (pin "RLMID") (pinfunction "P2_RLMID") (pintype "bidirectional"))
    )
    (net (code "28") (name "Net-(DS15-AN-PadANOST)") (class "Default")
      (node (ref "DS15") (pin "ANOST") (pinfunction "AN_ANOST") (pintype "bidirectional"))
      (node (ref "DS15") (pin "ANOT") (pinfunction "AN_ANOT") (pintype "bidirectional"))
      (node (ref "SWI15") (pin "MMR") (pinfunction "P2_MMR") (pintype "bidirectional"))
      (node (ref "SWI15") (pin "RCL") (pinfunction "P2_RCL") (pintype "bidirectional"))
      (node (ref "SWI15") (pin "RLMID") (pinfunction "P2_RLMID") (pintype "bidirectional"))
    )
    (net (code "29") (name "Net-(DS16-AN-PadANOST)") (class "Default")
      (node (ref "DS16") (pin "ANOST") (pinfunction "AN_ANOST") (pintype "bidirectional"))
      (node (ref "DS16") (pin "ANOT") (pinfunction "AN_ANOT") (pintype "bidirectional"))
      (node (ref "SWI16") (pin "MMR") (pinfunction "P2_MMR") (pintype "bidirectional"))
      (node (ref "SWI16") (pin "RCL") (pinfunction "P2_RCL") (pintype "bidirectional"))
      (node (ref "SWI16") (pin "RLMID") (pinfunction "P2_RLMID") (pintype "bidirectional"))
    )
    (net (code "30") (name "Net-(DS17-AN-PadANOST)") (class "Default")
      (node (ref "DS17") (pin "ANOST") (pinfunction "AN_ANOST") (pintype "bidirectional"))
      (node (ref "DS17") (pin "ANOT") (pinfunction "AN_ANOT") (pintype "bidirectional"))
      (node (ref "SWI17") (pin "MMR") (pinfunction "P2_MMR") (pintype "bidirectional"))
      (node (ref "SWI17") (pin "RCL") (pinfunction "P2_RCL") (pintype "bidirectional"))
      (node (ref "SWI17") (pin "RLMID") (pinfunction "P2_RLMID") (pintype "bidirectional"))
    )
    (net (code "31") (name "Net-(DS18-AN-PadANOST)") (class "Default")
      (node (ref "DS18") (pin "ANOST") (pinfunction "AN_ANOST") (pintype "bidirectional"))
      (node (ref "DS18") (pin "ANOT") (pinfunction "AN_ANOT") (pintype "bidirectional"))
      (node (ref "SWI18") (pin "MMR") (pinfunction "P2_MMR") (pintype "bidirectional"))
      (node (ref "SWI18") (pin "RCL") (pinfunction "P2_RCL") (pintype "bidirectional"))
      (node (ref "SWI18") (pin "RLMID") (pinfunction "P2_RLMID") (pintype "bidirectional"))
    )
    (net (code "32") (name "Net-(J1-CC1)") (class "Default")
      (node (ref "J1") (pin "A5") (pinfunction "CC1_A5") (pintype "bidirectional"))
      (node (ref "J1") (pin "B5") (pinfunction "CC2_B5") (pintype "bidirectional"))
      (node (ref "R1") (pin "2") (pinfunction "2_2") (pintype "passive"))
    )
    (net (code "33") (name "Net-(LED1-PadC)") (class "Default")
      (node (ref "LED1") (pin "C") (pinfunction "C_C") (pintype "passive"))
      (node (ref "R2") (pin "1") (pinfunction "1_1") (pintype "passive"))
    )
    (net (code "34") (name "Net-(R7-Pad1)") (class "Default")
      (node (ref "R7") (pin "1") (pinfunction "1_1") (pintype "passive"))
      (node (ref "SW3") (pin "COMM") (pinfunction "COMM_COMM") (pintype "passive"))
      (node (ref "U3") (pin "VIN") (pinfunction "VIN_VIN") (pintype "power_in"))
    )
    (net (code "35") (name "Net-(R7-Pad2)") (class "Default")
      (node (ref "R7") (pin "2") (pinfunction "2_2") (pintype "passive"))
      (node (ref "U3") (pin "CTRL") (pinfunction "CTRL_CTRL") (pintype "passive"))
    )
    (net (code "36") (name "Net-(U2-PROG)") (class "Default")
      (node (ref "R3") (pin "2") (pinfunction "2_2") (pintype "passive"))
      (node (ref "U2") (pin "5") (pinfunction "PROG_5") (pintype "passive"))
    )
    (net (code "37") (name "Net-(U2-STAT)") (class "Default")
      (node (ref "R2") (pin "2") (pinfunction "2_2") (pintype "passive"))
      (node (ref "U2") (pin "1") (pinfunction "STAT_1") (pintype "passive"))
    )
    (net (code "38") (name "Net-(U4-RST)") (class "Default")
      (node (ref "R8") (pin "2") (pinfunction "2_2") (pintype "passive"))
      (node (ref "U4") (pin "9") (pinfunction "RST_9") (pintype "input"))
    )
    (net (code "39") (name "Net-(U4-VBUS)") (class "Default")
      (node (ref "R10") (pin "2") (pinfunction "2_2") (pintype "passive"))
      (node (ref "R9") (pin "1") (pinfunction "1_1") (pintype "passive"))
      (node (ref "U4") (pin "8") (pinfunction "VBUS_8") (pintype "power_in"))
    )
    (net (code "40") (name "RESET") (class "Default")
      (node (ref "SW1") (pin "A1") (pinfunction "P$1_A1") (pintype "bidirectional"))
      (node (ref "SW1") (pin "A2") (pinfunction "P$1_A2") (pintype "bidirectional"))
      (node (ref "SW1") (pin "A3") (pinfunction "P$1_A3") (pintype "bidirectional"))
      (node (ref "SW1") (pin "A4") (pinfunction "P$1_A4") (pintype "bidirectional"))
      (node (ref "U1") (pin "7") (pinfunction "~{NRESET}_7") (pintype "input"))
    )
    (net (code "41") (name "ROW1") (class "Default")
      (node (ref "DS1") (pin "CATST") (pinfunction "CAT_CATST") (pintype "bidirectional"))
      (node (ref "DS1") (pin "CATT") (pinfunction "CAT_CATT") (pintype "bidirectional"))
      (node (ref "DS10") (pin "CATST") (pinfunction "CAT_CATST") (pintype "bidirectional"))
      (node (ref "DS10") (pin "CATT") (pinfunction "CAT_CATT") (pintype "bidirectional"))
      (node (ref "DS13") (pin "CATST") (pinfunction "CAT_CATST") (pintype "bidirectional"))
      (node (ref "DS13") (pin "CATT") (pinfunction "CAT_CATT") (pintype "bidirectional"))
      (node (ref "DS16") (pin "CATST") (pinfunction "CAT_CATST") (pintype "bidirectional"))
      (node (ref "DS16") (pin "CATT") (pinfunction "CAT_CATT") (pintype "bidirectional"))
      (node (ref "DS4") (pin "CATST") (pinfunction "CAT_CATST") (pintype "bidirectional"))
      (node (ref "DS4") (pin "CATT") (pinfunction "CAT_CATT") (pintype "bidirectional"))
      (node (ref "DS7") (pin "CATST") (pinfunction "CAT_CATST") (pintype "bidirectional"))
      (node (ref "DS7") (pin "CATT") (pinfunction "CAT_CATT") (pintype "bidirectional"))
      (node (ref "U1") (pin "2") (pinfunction "SIO_24/SPI_MISO_2") (pintype "bidirectional"))
    )
    (net (code "42") (name "ROW2") (class "Default")
      (node (ref "DS11") (pin "CATST") (pinfunction "CAT_CATST") (pintype "bidirectional"))
      (node (ref "DS11") (pin "CATT") (pinfunction "CAT_CATT") (pintype "bidirectional"))
      (node (ref "DS14") (pin "CATST") (pinfunction "CAT_CATST") (pintype "bidirectional"))
      (node (ref "DS14") (pin "CATT") (pinfunction "CAT_CATT") (pintype "bidirectional"))
      (node (ref "DS17") (pin "CATST") (pinfunction "CAT_CATST") (pintype "bidirectional"))
      (node (ref "DS17") (pin "CATT") (pinfunction "CAT_CATT") (pintype "bidirectional"))
      (node (ref "DS2") (pin "CATST") (pinfunction "CAT_CATST") (pintype "bidirectional"))
      (node (ref "DS2") (pin "CATT") (pinfunction "CAT_CATT") (pintype "bidirectional"))
      (node (ref "DS5") (pin "CATST") (pinfunction "CAT_CATST") (pintype "bidirectional"))
      (node (ref "DS5") (pin "CATT") (pinfunction "CAT_CATT") (pintype "bidirectional"))
      (node (ref "DS8") (pin "CATST") (pinfunction "CAT_CATST") (pintype "bidirectional"))
      (node (ref "DS8") (pin "CATT") (pinfunction "CAT_CATT") (pintype "bidirectional"))
      (node (ref "U1") (pin "38") (pinfunction "SIO_25/SPI_CLK_38") (pintype "bidirectional"))
    )
    (net (code "43") (name "ROW3") (class "Default")
      (node (ref "DS12") (pin "CATST") (pinfunction "CAT_CATST") (pintype "bidirectional"))
      (node (ref "DS12") (pin "CATT") (pinfunction "CAT_CATT") (pintype "bidirectional"))
      (node (ref "DS15") (pin "CATST") (pinfunction "CAT_CATST") (pintype "bidirectional"))
      (node (ref "DS15") (pin "CATT") (pinfunction "CAT_CATT") (pintype "bidirectional"))
      (node (ref "DS18") (pin "CATST") (pinfunction "CAT_CATST") (pintype "bidirectional"))
      (node (ref "DS18") (pin "CATT") (pinfunction "CAT_CATT") (pintype "bidirectional"))
      (node (ref "DS3") (pin "CATST") (pinfunction "CAT_CATST") (pintype "bidirectional"))
      (node (ref "DS3") (pin "CATT") (pinfunction "CAT_CATT") (pintype "bidirectional"))
      (node (ref "DS6") (pin "CATST") (pinfunction "CAT_CATST") (pintype "bidirectional"))
      (node (ref "DS6") (pin "CATT") (pinfunction "CAT_CATT") (pintype "bidirectional"))
      (node (ref "DS9") (pin "CATST") (pinfunction "CAT_CATST") (pintype "bidirectional"))
      (node (ref "DS9") (pin "CATT") (pinfunction "CAT_CATT") (pintype "bidirectional"))
      (node (ref "U1") (pin "37") (pinfunction "SIO_26/I2C_SDA_37") (pintype "bidirectional"))
    )
    (net (code "44") (name "ROW4") (class "Default")
      (node (ref "U1") (pin "36") (pinfunction "SIO_27/I2C_SCL_36") (pintype "bidirectional"))
    )
    (net (code "45") (name "ROW5T1") (class "Default")
      (node (ref "INT1") (pin "T1") (pinfunction "T1_T1") (pintype "bidirectional"))
      (node (ref "U1") (pin "35") (pinfunction "SIO_28/AIN4_35") (pintype "bidirectional"))
    )
    (net (code "46") (name "ROW6T2") (class "Default")
      (node (ref "INT1") (pin "T2") (pinfunction "T2_T2") (pintype "bidirectional"))
      (node (ref "U1") (pin "34") (pinfunction "SIO_29/AIN5_34") (pintype "bidirectional"))
    )
    (net (code "47") (name "RX0") (class "Default")
      (node (ref "J3") (pin "5") (pinfunction "5_5") (pintype "passive"))
      (node (ref "U1") (pin "17") (pinfunction "SIO_08/UART_RX_17") (pintype "bidirectional"))
      (node (ref "U4") (pin "17") (pinfunction "RXD_17") (pintype "input"))
    )
    (net (code "48") (name "SWDCLK") (class "Default")
      (node (ref "J2") (pin "2") (pinfunction "2_2") (pintype "passive"))
      (node (ref "U1") (pin "6") (pinfunction "SWDCLK_6") (pintype "input"))
    )
    (net (code "49") (name "SWDIO") (class "Default")
      (node (ref "J2") (pin "3") (pinfunction "3_3") (pintype "passive"))
      (node (ref "U1") (pin "5") (pinfunction "SWDIO_5") (pintype "bidirectional"))
    )
    (net (code "50") (name "TX0") (class "Default")
      (node (ref "J3") (pin "4") (pinfunction "4_4") (pintype "passive"))
      (node (ref "U1") (pin "19") (pinfunction "SIO_06/UART_TX_19") (pintype "bidirectional"))
      (node (ref "U4") (pin "18") (pinfunction "TXD_18") (pintype "output"))
    )
    (net (code "51") (name "V_BATT") (class "Default")
      (node (ref "C2") (pin "1") (pinfunction "1_1") (pintype "passive"))
      (node (ref "JP1") (pin "1") (pinfunction "1_1") (pintype "passive"))
      (node (ref "R5") (pin "2") (pinfunction "2_2") (pintype "passive"))
      (node (ref "T1") (pin "C") (pinfunction "C_C") (pintype "passive"))
      (node (ref "U2") (pin "3") (pinfunction "VBAT_3") (pintype "passive"))
    )
    (net (code "52") (name "V_USB") (class "Default")
      (node (ref "D1") (pin "A") (pinfunction "A_A") (pintype "passive"))
      (node (ref "J1") (pin "A4") (pinfunction "VBUS_A4") (pintype "bidirectional"))
      (node (ref "J1") (pin "A9") (pinfunction "VBUS_A9") (pintype "bidirectional"))
      (node (ref "J1") (pin "B4") (pinfunction "VBUS_B4") (pintype "bidirectional"))
      (node (ref "J1") (pin "B9") (pinfunction "VBUS_B9") (pintype "bidirectional"))
      (node (ref "J3") (pin "3") (pinfunction "3_3") (pintype "passive"))
      (node (ref "LED1") (pin "A") (pinfunction "A_A") (pintype "passive"))
      (node (ref "R4") (pin "2") (pinfunction "2_2") (pintype "passive"))
      (node (ref "R9") (pin "2") (pinfunction "2_2") (pintype "passive"))
      (node (ref "T1") (pin "B") (pinfunction "B_B") (pintype "passive"))
      (node (ref "U2") (pin "4") (pinfunction "VDD_4") (pintype "passive"))
      (node (ref "U4") (pin "7") (pinfunction "VREGIN_7") (pintype "power_in"))
    )
    (net (code "53") (name "unconnected-(J3-Pad2)") (class "Default")
      (node (ref "J3") (pin "2") (pinfunction "2_2") (pintype "passive"))
    )
    (net (code "54") (name "unconnected-(J3-Pad6)") (class "Default")
      (node (ref "J3") (pin "6") (pinfunction "6_6") (pintype "passive"))
    )
    (net (code "55") (name "unconnected-(SW3-Pad2)") (class "Default")
      (node (ref "SW3") (pin "2") (pinfunction "2_2") (pintype "passive"))
    )
    (net (code "56") (name "unconnected-(U1-NFC1{slash}SIO_09-Pad15)") (class "Default")
      (node (ref "U1") (pin "15") (pinfunction "NFC1/SIO_09_15") (pintype "bidirectional"))
    )
    (net (code "57") (name "unconnected-(U1-NFC2{slash}SIO_10-Pad14)") (class "Default")
      (node (ref "U1") (pin "14") (pinfunction "NFC2/SIO_10_14") (pintype "bidirectional"))
    )
    (net (code "58") (name "unconnected-(U1-SIO_00{slash}XL1-Pad25)") (class "Default")
      (node (ref "U1") (pin "25") (pinfunction "SIO_00/XL1_25") (pintype "bidirectional"))
    )
    (net (code "59") (name "unconnected-(U1-SIO_01{slash}XL2-Pad24)") (class "Default")
      (node (ref "U1") (pin "24") (pinfunction "SIO_01/XL2_24") (pintype "bidirectional"))
    )
    (net (code "60") (name "unconnected-(U1-SIO_02{slash}AIN0-Pad23)") (class "Default")
      (node (ref "U1") (pin "23") (pinfunction "SIO_02/AIN0_23") (pintype "bidirectional"))
    )
    (net (code "61") (name "unconnected-(U1-SIO_03{slash}AIN1-Pad22)") (class "Default")
      (node (ref "U1") (pin "22") (pinfunction "SIO_03/AIN1_22") (pintype "bidirectional"))
    )
    (net (code "62") (name "unconnected-(U1-SIO_04{slash}AIN2-Pad21)") (class "Default")
      (node (ref "U1") (pin "21") (pinfunction "SIO_04/AIN2_21") (pintype "bidirectional"))
    )
    (net (code "63") (name "unconnected-(U1-SIO_05{slash}UART_RTS{slash}AIN3-Pad20)") (class "Default")
      (node (ref "U1") (pin "20") (pinfunction "SIO_05/UART_RTS/AIN3_20") (pintype "bidirectional"))
    )
    (net (code "64") (name "unconnected-(U1-SIO_07{slash}UART_CTS-Pad18)") (class "Default")
      (node (ref "U1") (pin "18") (pinfunction "SIO_07/UART_CTS_18") (pintype "bidirectional"))
    )
    (net (code "65") (name "unconnected-(U1-SIO_17-Pad30)") (class "Default")
      (node (ref "U1") (pin "30") (pinfunction "SIO_17_30") (pintype "bidirectional"))
    )
    (net (code "66") (name "unconnected-(U1-SIO_18-Pad9)") (class "Default")
      (node (ref "U1") (pin "9") (pinfunction "SIO_18_9") (pintype "bidirectional"))
    )
    (net (code "67") (name "unconnected-(U1-SIO_19-Pad31)") (class "Default")
      (node (ref "U1") (pin "31") (pinfunction "SIO_19_31") (pintype "bidirectional"))
    )
    (net (code "68") (name "unconnected-(U1-SIO_22-Pad4)") (class "Default")
      (node (ref "U1") (pin "4") (pinfunction "SIO_22_4") (pintype "bidirectional"))
    )
    (net (code "69") (name "unconnected-(U1-SIO_23{slash}SPI_MOSI-Pad3)") (class "Default")
      (node (ref "U1") (pin "3") (pinfunction "SIO_23/SPI_MOSI_3") (pintype "bidirectional"))
    )
    (net (code "70") (name "unconnected-(U1-SIO_30{slash}AIN6-Pad33)") (class "Default")
      (node (ref "U1") (pin "33") (pinfunction "SIO_30/AIN6_33") (pintype "bidirectional"))
    )
    (net (code "71") (name "unconnected-(U3-PadNC)") (class "Default")
      (node (ref "U3") (pin "NC") (pinfunction "NC_NC") (pintype "no_connect"))
    )
    (net (code "72") (name "unconnected-(U4-CTS-Pad15)") (class "Default")
      (node (ref "U4") (pin "15") (pinfunction "CTS_15") (pintype "input"))
    )
    (net (code "73") (name "unconnected-(U4-GPIO.0{slash}CLK-Pad2)") (class "Default")
      (node (ref "U4") (pin "2") (pinfunction "GPIO.0/CLK_2") (pintype "bidirectional"))
    )
    (net (code "74") (name "unconnected-(U4-GPIO.1{slash}RS485-Pad1)") (class "Default")
      (node (ref "U4") (pin "1") (pinfunction "GPIO.1/RS485_1") (pintype "bidirectional"))
    )
    (net (code "75") (name "unconnected-(U4-GPIO.2{slash}TXT-Pad20)") (class "Default")
      (node (ref "U4") (pin "20") (pinfunction "GPIO.2/TXT_20") (pintype "bidirectional"))
    )
    (net (code "76") (name "unconnected-(U4-GPIO.3{slash}RXT-Pad19)") (class "Default")
      (node (ref "U4") (pin "19") (pinfunction "GPIO.3/RXT_19") (pintype "bidirectional"))
    )
    (net (code "77") (name "unconnected-(U4-NC-Pad10)") (class "Default")
      (node (ref "U4") (pin "10") (pinfunction "NC_10") (pintype "no_connect"))
    )
    (net (code "78") (name "unconnected-(U4-RTS-Pad16)") (class "Default")
      (node (ref "U4") (pin "16") (pinfunction "RTS_16") (pintype "output"))
    )
    (net (code "79") (name "unconnected-(U4-SUSPEND-Pad14)") (class "Default")
      (node (ref "U4") (pin "14") (pinfunction "SUSPEND_14") (pintype "output"))
    )
    (net (code "80") (name "unconnected-(U4-SUSPENDB-Pad11)") (class "Default")
      (node (ref "U4") (pin "11") (pinfunction "SUSPENDB_11") (pintype "output"))
    )
    (net (code "81") (name "unconnected-(U4-WAKEUP-Pad13)") (class "Default")
      (node (ref "U4") (pin "13") (pinfunction "WAKEUP_13") (pintype "input"))
    )
  )
)
